# eDP.net
KiCad netlist of a schematic drawn in Altium Designer
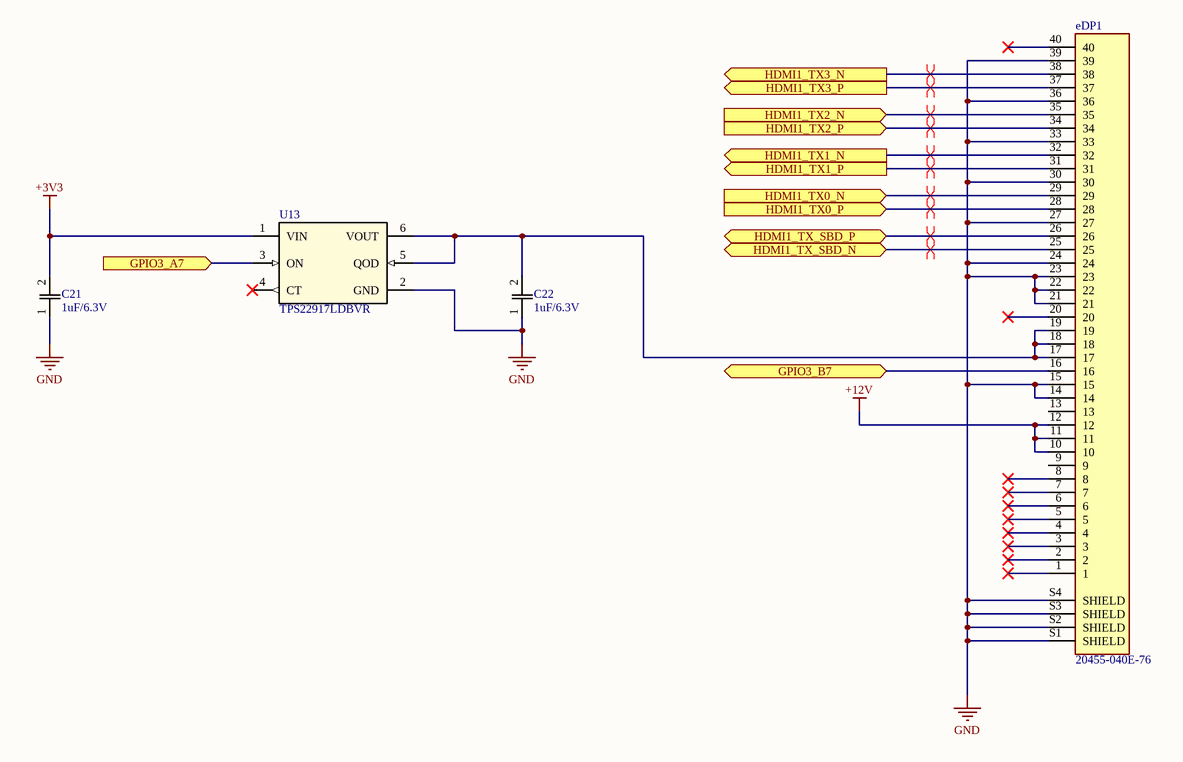
[diagram p0: eDP.SchDoc]

(export (version "E")
  (design (tool "Eeschema 10.0.6"))
  (components
    (comp (ref "C21")
      (value "1uF/6.3V")
      (footprint "SamacSys:C0805")
      (description "1 uF, 6.3 V, ± 10%, X7R, 0805 [2012 Metric] Multilayer Ceramic Capacitor,")
      (fields
        (field (name "MANUFACTURER_PART_NUMBER") "C0805C105K9RACTU")
        (field (name "MOUSER PART NUMBER") "80-C0805C105K9R")
      )
      (libsource (lib "SamacSys") (part "C0805C105K9RACTU"))
    )
    (comp (ref "C22")
      (value "1uF/6.3V")
      (footprint "SamacSys:C0805")
      (description "1 uF, 6.3 V, ± 10%, X7R, 0805 [2012 Metric] Multilayer Ceramic Capacitor,")
      (fields
        (field (name "MANUFACTURER_PART_NUMBER") "C0805C105K9RACTU")
        (field (name "MOUSER PART NUMBER") "80-C0805C105K9R")
      )
      (libsource (lib "SamacSys") (part "C0805C105K9RACTU"))
    )
    (comp (ref "eDP1")
      (value "20455-040E-76")
      (footprint "IPEX_20455-040E-76:IPEX_20455-040E-76")
      (description "Conn Wire to Board RCP 40 POS 0.5mm Solder RA Side Entry SMDCABLINE® T/R")
      (fields (field (name "MANUFACTURER") "I-PEX"))
      (libsource (lib "20455-040E-76") (part "20455-040E-76"))
    )
    (comp (ref "U13")
      (value "TPS22917LDBVR")
      (footprint "DBV0006_L")
      (fields (field (name "MANUFACTURER") "Texas Instruments"))
      (libsource (lib "TPS22917LDBVR") (part "TPS22917LDBVR"))
    )
  )
  (nets
    (net (code "1") (name "+3V3") (class "Default")
      (node (ref "C21") (pin "2") (pinfunction "2_2") (pintype "passive"))
      (node (ref "U13") (pin "1") (pinfunction "VIN_1") (pintype "power_in"))
    )
    (net (code "2") (name "+12V") (class "Default")
      (node (ref "eDP1") (pin "10") (pinfunction "10_10") (pintype "passive"))
      (node (ref "eDP1") (pin "11") (pinfunction "11_11") (pintype "passive"))
      (node (ref "eDP1") (pin "12") (pinfunction "12_12") (pintype "passive"))
    )
    (net (code "3") (name "/GPIO3_A7") (class "Default")
      (node (ref "U13") (pin "3") (pinfunction "ON_3") (pintype "input"))
    )
    (net (code "4") (name "/GPIO3_B7") (class "Default")
      (node (ref "eDP1") (pin "16") (pinfunction "16_16") (pintype "passive"))
    )
    (net (code "5") (name "/HDMI1_TX0_N") (class "Default")
      (node (ref "eDP1") (pin "29") (pinfunction "29_29") (pintype "passive"))
    )
    (net (code "6") (name "/HDMI1_TX0_P") (class "Default")
      (node (ref "eDP1") (pin "28") (pinfunction "28_28") (pintype "passive"))
    )
    (net (code "7") (name "/HDMI1_TX1_N") (class "Default")
      (node (ref "eDP1") (pin "32") (pinfunction "32_32") (pintype "passive"))
    )
    (net (code "8") (name "/HDMI1_TX1_P") (class "Default")
      (node (ref "eDP1") (pin "31") (pinfunction "31_31") (pintype "passive"))
    )
    (net (code "9") (name "/HDMI1_TX2_N") (class "Default")
      (node (ref "eDP1") (pin "35") (pinfunction "35_35") (pintype "passive"))
    )
    (net (code "10") (name "/HDMI1_TX2_P") (class "Default")
      (node (ref "eDP1") (pin "34") (pinfunction "34_34") (pintype "passive"))
    )
    (net (code "11") (name "/HDMI1_TX3_N") (class "Default")
      (node (ref "eDP1") (pin "38") (pinfunction "38_38") (pintype "passive"))
    )
    (net (code "12") (name "/HDMI1_TX3_P") (class "Default")
      (node (ref "eDP1") (pin "37") (pinfunction "37_37") (pintype "passive"))
    )
    (net (code "13") (name "/HDMI1_TX_SBD_N") (class "Default")
      (node (ref "eDP1") (pin "25") (pinfunction "25_25") (pintype "passive"))
    )
    (net (code "14") (name "/HDMI1_TX_SBD_P") (class "Default")
      (node (ref "eDP1") (pin "26") (pinfunction "26_26") (pintype "passive"))
    )
    (net (code "15") (name "GND") (class "Default")
      (node (ref "C21") (pin "1") (pinfunction "1_1") (pintype "passive"))
      (node (ref "C22") (pin "1") (pinfunction "1_1") (pintype "passive"))
      (node (ref "U13") (pin "2") (pinfunction "GND_2") (pintype "passive"))
      (node (ref "eDP1") (pin "14") (pinfunction "14_14") (pintype "passive"))
      (node (ref "eDP1") (pin "15") (pinfunction "15_15") (pintype "passive"))
      (node (ref "eDP1") (pin "21") (pinfunction "21_21") (pintype "passive"))
      (node (ref "eDP1") (pin "22") (pinfunction "22_22") (pintype "passive"))
      (node (ref "eDP1") (pin "23") (pinfunction "23_23") (pintype "passive"))
      (node (ref "eDP1") (pin "24") (pinfunction "24_24") (pintype "passive"))
      (node (ref "eDP1") (pin "27") (pinfunction "27_27") (pintype "passive"))
      (node (ref "eDP1") (pin "30") (pinfunction "30_30") (pintype "passive"))
      (node (ref "eDP1") (pin "33") (pinfunction "33_33") (pintype "passive"))
      (node (ref "eDP1") (pin "36") (pinfunction "36_36") (pintype "passive"))
      (node (ref "eDP1") (pin "39") (pinfunction "39_39") (pintype "passive"))
      (node (ref "eDP1") (pin "S1") (pinfunction "SHIELD_S1") (pintype "passive"))
      (node (ref "eDP1") (pin "S2") (pinfunction "SHIELD_S2") (pintype "passive"))
      (node (ref "eDP1") (pin "S3") (pinfunction "SHIELD_S3") (pintype "passive"))
      (node (ref "eDP1") (pin "S4") (pinfunction "SHIELD_S4") (pintype "passive"))
    )
    (net (code "16") (name "Net-(U13-QOD)") (class "Default")
      (node (ref "C22") (pin "2") (pinfunction "2_2") (pintype "passive"))
      (node (ref "U13") (pin "5") (pinfunction "QOD_5") (pintype "input"))
      (node (ref "U13") (pin "6") (pinfunction "VOUT_6") (pintype "power_in"))
      (node (ref "eDP1") (pin "17") (pinfunction "17_17") (pintype "passive"))
      (node (ref "eDP1") (pin "18") (pinfunction "18_18") (pintype "passive"))
      (node (ref "eDP1") (pin "19") (pinfunction "19_19") (pintype "passive"))
    )
    (net (code "17") (name "unconnected-(U13-CT-Pad4)") (class "Default")
      (node (ref "U13") (pin "4") (pinfunction "CT_4") (pintype "output+no_connect"))
    )
    (net (code "18") (name "unconnected-(eDP1-Pad1)") (class "Default")
      (node (ref "eDP1") (pin "1") (pinfunction "1_1") (pintype "passive+no_connect"))
    )
    (net (code "19") (name "unconnected-(eDP1-Pad2)") (class "Default")
      (node (ref "eDP1") (pin "2") (pinfunction "2_2") (pintype "passive+no_connect"))
    )
    (net (code "20") (name "unconnected-(eDP1-Pad3)") (class "Default")
      (node (ref "eDP1") (pin "3") (pinfunction "3_3") (pintype "passive+no_connect"))
    )
    (net (code "21") (name "unconnected-(eDP1-Pad4)") (class "Default")
      (node (ref "eDP1") (pin "4") (pinfunction "4_4") (pintype "passive+no_connect"))
    )
    (net (code "22") (name "unconnected-(eDP1-Pad5)") (class "Default")
      (node (ref "eDP1") (pin "5") (pinfunction "5_5") (pintype "passive+no_connect"))
    )
    (net (code "23") (name "unconnected-(eDP1-Pad6)") (class "Default")
      (node (ref "eDP1") (pin "6") (pinfunction "6_6") (pintype "passive+no_connect"))
    )
    (net (code "24") (name "unconnected-(eDP1-Pad7)") (class "Default")
      (node (ref "eDP1") (pin "7") (pinfunction "7_7") (pintype "passive+no_connect"))
    )
    (net (code "25") (name "unconnected-(eDP1-Pad8)") (class "Default")
      (node (ref "eDP1") (pin "8") (pinfunction "8_8") (pintype "passive+no_connect"))
    )
    (net (code "26") (name "unconnected-(eDP1-Pad9)") (class "Default")
      (node (ref "eDP1") (pin "9") (pinfunction "9_9") (pintype "passive"))
    )
    (net (code "27") (name "unconnected-(eDP1-Pad13)") (class "Default")
      (node (ref "eDP1") (pin "13") (pinfunction "13_13") (pintype "passive"))
    )
    (net (code "28") (name "unconnected-(eDP1-Pad20)") (class "Default")
      (node (ref "eDP1") (pin "20") (pinfunction "20_20") (pintype "passive+no_connect"))
    )
    (net (code "29") (name "unconnected-(eDP1-Pad40)") (class "Default")
      (node (ref "eDP1") (pin "40") (pinfunction "40_40") (pintype "passive+no_connect"))
    )
  )
)
